# MesschieberV7.net
KiCad netlist of a schematic drawn in EAGLE
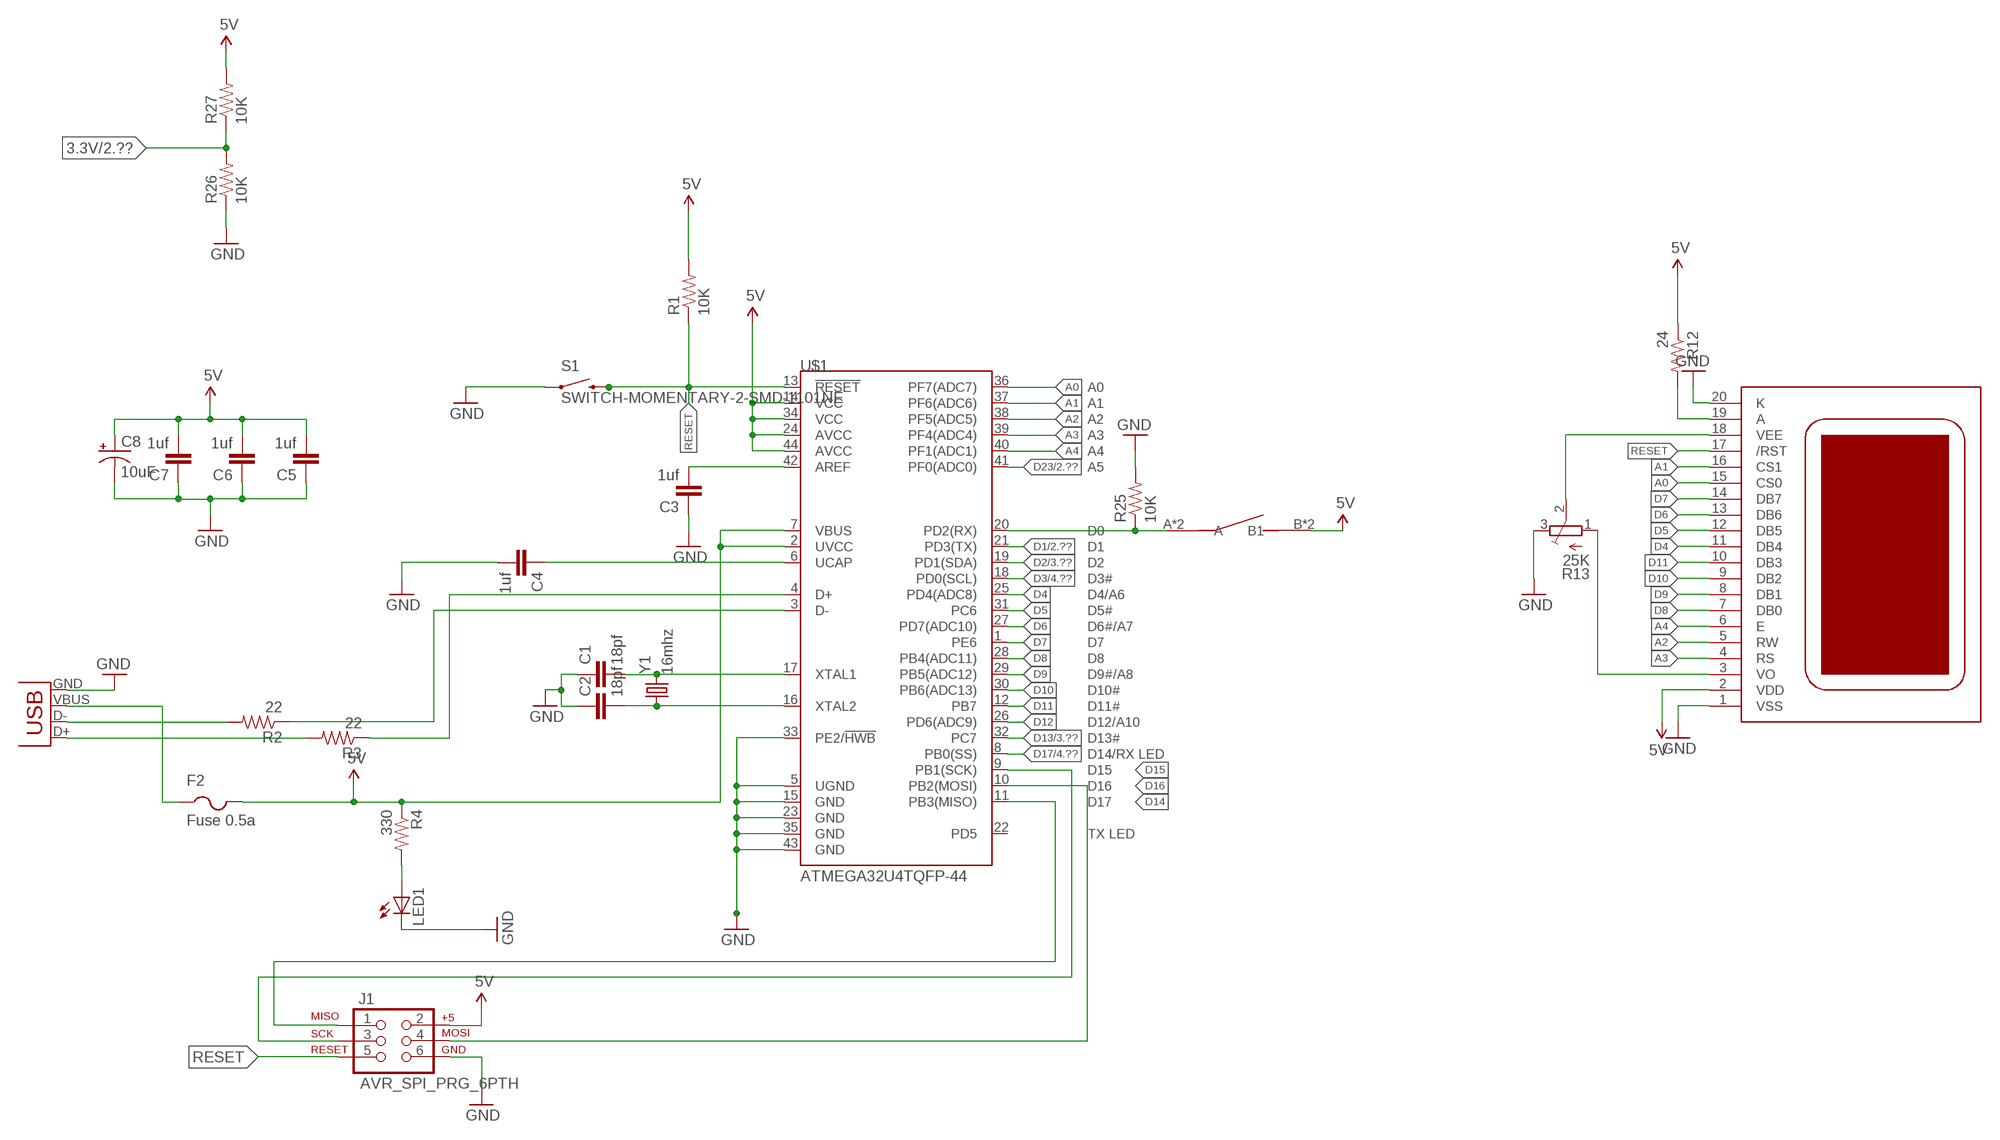
[diagram p0: schematic, sheet 1]
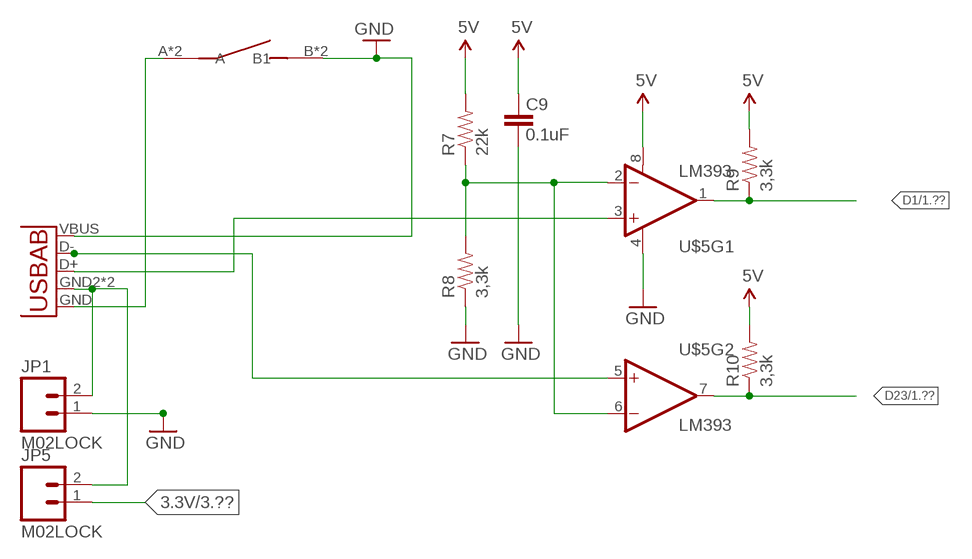
[diagram p1: schematic, sheet 2]
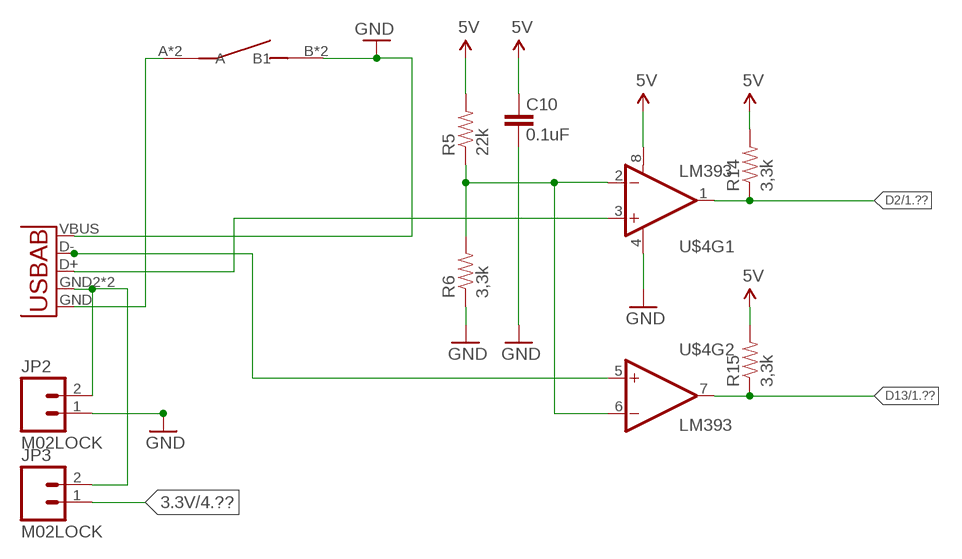
[diagram p2: schematic, sheet 3]
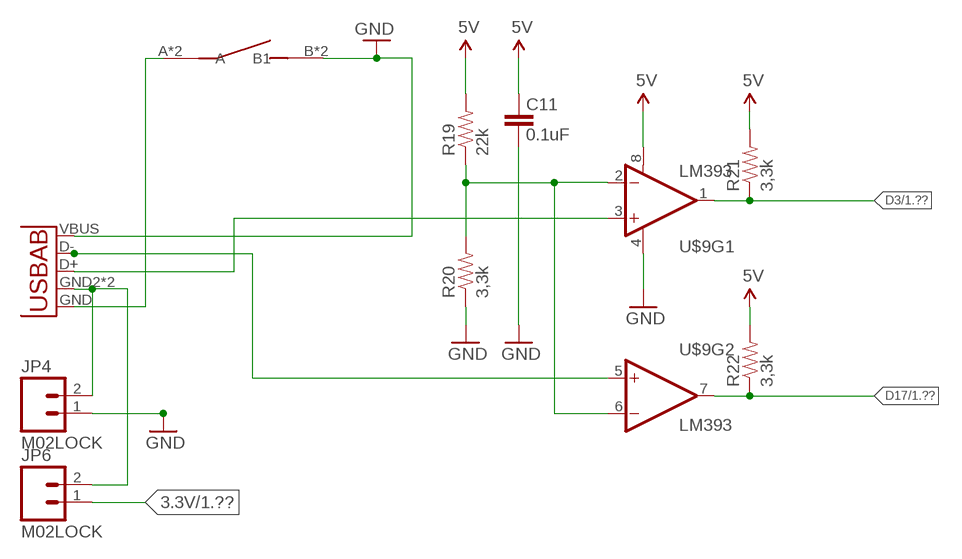
[diagram p3: schematic, sheet 4]

(export (version "E")
  (design (tool "Eeschema 10.0.6"))
  (components
    (comp (ref "C10")
      (value "0.1uF")
      (footprint "eagle-import:0805")
      (libsource (lib "eagle-import") (part "CAP0805"))
    )
    (comp (ref "JP2")
      (value "M02LOCK")
      (footprint "eagle-import:1X02_LOCK")
      (libsource (lib "eagle-import") (part "M02LOCK"))
    )
    (comp (ref "JP3")
      (value "M02LOCK")
      (footprint "eagle-import:1X02_LOCK")
      (libsource (lib "eagle-import") (part "M02LOCK"))
    )
    (comp (ref "R5")
      (value "22k")
      (footprint "eagle-import:0603")
      (libsource (lib "eagle-import") (part "RESISTOR0603"))
    )
    (comp (ref "R6")
      (value "3,3k")
      (footprint "eagle-import:0603")
      (libsource (lib "eagle-import") (part "RESISTOR0603"))
    )
    (comp (ref "R14")
      (value "3,3k")
      (footprint "eagle-import:0603")
      (libsource (lib "eagle-import") (part "RESISTOR0603"))
    )
    (comp (ref "R15")
      (value "3,3k")
      (footprint "eagle-import:0603")
      (libsource (lib "eagle-import") (part "RESISTOR0603"))
    )
    (comp (ref "U$4")
      (value "LM393")
      (footprint "eagle-import:SO08")
      (libsource (lib "eagle-import") (part "LM393"))
    )
    (comp (ref "U$6")
      (value "USB-A")
      (footprint "eagle-import:USB-A")
      (libsource (lib "eagle-import") (part "USB-A"))
    )
    (comp (ref "U$8")
      (value "TASTE_R3FTL6")
      (footprint "eagle-import:TASTE_R3FTL6")
      (libsource (lib "eagle-import") (part "TASTE_R3FTL6"))
    )
    (comp (ref "C1")
      (value "18pf")
      (footprint "eagle-import:0805")
      (libsource (lib "eagle-import") (part "SparkFun-Capacitors_CAP0805"))
    )
    (comp (ref "C2")
      (value "18pf")
      (footprint "eagle-import:0805")
      (libsource (lib "eagle-import") (part "SparkFun-Capacitors_CAP0805"))
    )
    (comp (ref "C3")
      (value "1uf")
      (footprint "eagle-import:0805")
      (libsource (lib "eagle-import") (part "SparkFun-Capacitors_CAP0805"))
    )
    (comp (ref "C4")
      (value "1uf")
      (footprint "eagle-import:0805")
      (libsource (lib "eagle-import") (part "SparkFun-Capacitors_CAP0805"))
    )
    (comp (ref "C5")
      (value "1uf")
      (footprint "eagle-import:0805")
      (libsource (lib "eagle-import") (part "SparkFun-Capacitors_CAP0805"))
    )
    (comp (ref "C6")
      (value "1uf")
      (footprint "eagle-import:0805")
      (libsource (lib "eagle-import") (part "SparkFun-Capacitors_CAP0805"))
    )
    (comp (ref "C7")
      (value "1uf")
      (footprint "eagle-import:0805")
      (libsource (lib "eagle-import") (part "SparkFun-Capacitors_CAP0805"))
    )
    (comp (ref "C8")
      (value "10uF")
      (footprint "eagle-import:EIA3528")
      (libsource (lib "eagle-import") (part "10UF-20V-10%(TANT)"))
    )
    (comp (ref "F2")
      (value "Fuse 0.5a")
      (footprint "eagle-import:1812")
      (libsource (lib "eagle-import") (part "PTCFUSE-1812"))
    )
    (comp (ref "J1")
      (value "AVR_SPI_PRG_6PTH")
      (footprint "eagle-import:2X3")
      (libsource (lib "eagle-import") (part "AVR_SPI_PRG_6PTH"))
    )
    (comp (ref "JP7")
      (value "USB-SMD-NS")
      (footprint "eagle-import:USB-MINIB-NOSTOP")
      (libsource (lib "eagle-import") (part "USB-SMD-NS"))
    )
    (comp (ref "LED1")
      (value "LEDSML0805")
      (footprint "eagle-import:SML0805")
      (libsource (lib "eagle-import") (part "LEDSML0805"))
    )
    (comp (ref "R1")
      (value "10K")
      (footprint "eagle-import:0603-RES")
      (libsource (lib "eagle-import") (part "RESISTOR0603-RES"))
    )
    (comp (ref "R2")
      (value "22")
      (footprint "eagle-import:0603")
      (libsource (lib "eagle-import") (part "RESISTOR0603"))
    )
    (comp (ref "R3")
      (value "22")
      (footprint "eagle-import:0603")
      (libsource (lib "eagle-import") (part "RESISTOR0603"))
    )
    (comp (ref "R4")
      (value "330")
      (footprint "eagle-import:0603")
      (libsource (lib "eagle-import") (part "RESISTOR0603"))
    )
    (comp (ref "R12")
      (value "24")
      (footprint "eagle-import:0603")
      (libsource (lib "eagle-import") (part "RESISTOR0603"))
    )
    (comp (ref "R13")
      (value "25K")
      (footprint "eagle-import:SM-42_43A")
      (libsource (lib "eagle-import") (part "TRIM_EU-SM-42/43A"))
    )
    (comp (ref "R25")
      (value "10K")
      (footprint "eagle-import:0603")
      (libsource (lib "eagle-import") (part "RESISTOR0603"))
    )
    (comp (ref "R26")
      (value "10K")
      (footprint "eagle-import:0805")
      (libsource (lib "eagle-import") (part "RESISTOR"))
    )
    (comp (ref "R27")
      (value "10K")
      (footprint "eagle-import:0805")
      (libsource (lib "eagle-import") (part "RESISTOR"))
    )
    (comp (ref "S1")
      (value "SWITCH-MOMENTARY-2-SMD-1101NE")
      (footprint "eagle-import:TACTILE-SWITCH-1101NE")
      (libsource (lib "eagle-import") (part "SWITCH-MOMENTARY-2-SMD-1101NE"))
    )
    (comp (ref "U$1")
      (value "ATMEGA32U4TQFP-44")
      (footprint "eagle-import:TQFP44")
      (libsource (lib "eagle-import") (part "ATMEGA32U4TQFP-44"))
    )
    (comp (ref "U$2")
      (value "TS12864A")
      (footprint "eagle-import:TS12864")
      (libsource (lib "eagle-import") (part "TS12864A"))
    )
    (comp (ref "U$12")
      (value "TASTE_R3FTL6")
      (footprint "eagle-import:TASTE_R3FTL6")
      (libsource (lib "eagle-import") (part "TASTE_R3FTL6"))
    )
    (comp (ref "Y1")
      (value "16mhz")
      (footprint "eagle-import:CRYSTAL-SMD-5X3")
      (libsource (lib "eagle-import") (part "CRYSTAL5X3"))
    )
    (comp (ref "C11")
      (value "0.1uF")
      (footprint "eagle-import:0805")
      (libsource (lib "eagle-import") (part "CAP0805"))
    )
    (comp (ref "JP4")
      (value "M02LOCK")
      (footprint "eagle-import:1X02_LOCK")
      (libsource (lib "eagle-import") (part "M02LOCK"))
    )
    (comp (ref "JP6")
      (value "M02LOCK")
      (footprint "eagle-import:1X02_LOCK")
      (libsource (lib "eagle-import") (part "M02LOCK"))
    )
    (comp (ref "R19")
      (value "22k")
      (footprint "eagle-import:0603")
      (libsource (lib "eagle-import") (part "RESISTOR0603"))
    )
    (comp (ref "R20")
      (value "3,3k")
      (footprint "eagle-import:0603")
      (libsource (lib "eagle-import") (part "RESISTOR0603"))
    )
    (comp (ref "R21")
      (value "3,3k")
      (footprint "eagle-import:0603")
      (libsource (lib "eagle-import") (part "RESISTOR0603"))
    )
    (comp (ref "R22")
      (value "3,3k")
      (footprint "eagle-import:0603")
      (libsource (lib "eagle-import") (part "RESISTOR0603"))
    )
    (comp (ref "U$9")
      (value "LM393")
      (footprint "eagle-import:SO08")
      (libsource (lib "eagle-import") (part "LM393"))
    )
    (comp (ref "U$10")
      (value "USB-A")
      (footprint "eagle-import:USB-A")
      (libsource (lib "eagle-import") (part "USB-A"))
    )
    (comp (ref "U$11")
      (value "TASTE_R3FTL6")
      (footprint "eagle-import:TASTE_R3FTL6")
      (libsource (lib "eagle-import") (part "TASTE_R3FTL6"))
    )
    (comp (ref "C9")
      (value "0.1uF")
      (footprint "eagle-import:0805")
      (libsource (lib "eagle-import") (part "CAP0805"))
    )
    (comp (ref "JP1")
      (value "M02LOCK")
      (footprint "eagle-import:1X02_LOCK")
      (libsource (lib "eagle-import") (part "M02LOCK"))
    )
    (comp (ref "JP5")
      (value "M02LOCK")
      (footprint "eagle-import:1X02_LOCK")
      (libsource (lib "eagle-import") (part "M02LOCK"))
    )
    (comp (ref "R7")
      (value "22k")
      (footprint "eagle-import:0603")
      (libsource (lib "eagle-import") (part "RESISTOR0603"))
    )
    (comp (ref "R8")
      (value "3,3k")
      (footprint "eagle-import:0603")
      (libsource (lib "eagle-import") (part "RESISTOR0603"))
    )
    (comp (ref "R9")
      (value "3,3k")
      (footprint "eagle-import:0603")
      (libsource (lib "eagle-import") (part "RESISTOR0603"))
    )
    (comp (ref "R10")
      (value "3,3k")
      (footprint "eagle-import:0603")
      (libsource (lib "eagle-import") (part "RESISTOR0603"))
    )
    (comp (ref "U$3")
      (value "TASTE_R3FTL6")
      (footprint "eagle-import:TASTE_R3FTL6")
      (libsource (lib "eagle-import") (part "TASTE_R3FTL6"))
    )
    (comp (ref "U$5")
      (value "LM393")
      (footprint "eagle-import:SO08")
      (libsource (lib "eagle-import") (part "LM393"))
    )
    (comp (ref "U$7")
      (value "USB-A")
      (footprint "eagle-import:USB-A")
      (libsource (lib "eagle-import") (part "USB-A"))
    )
  )
  (nets
    (net (code "1") (name "3.3V") (class "Default")
      (node (ref "JP3") (pin "1") (pinfunction "1_1") (pintype "passive"))
      (node (ref "JP5") (pin "1") (pinfunction "1_1") (pintype "passive"))
      (node (ref "JP6") (pin "1") (pinfunction "1_1") (pintype "passive"))
      (node (ref "R26") (pin "2") (pinfunction "2_2") (pintype "passive"))
      (node (ref "R27") (pin "1") (pinfunction "1_1") (pintype "passive"))
    )
    (net (code "2") (name "5V") (class "Default")
      (node (ref "C10") (pin "2") (pinfunction "2_2") (pintype "passive"))
      (node (ref "C11") (pin "2") (pinfunction "2_2") (pintype "passive"))
      (node (ref "C5") (pin "2") (pinfunction "2_2") (pintype "passive"))
      (node (ref "C6") (pin "2") (pinfunction "2_2") (pintype "passive"))
      (node (ref "C7") (pin "2") (pinfunction "2_2") (pintype "passive"))
      (node (ref "C8") (pin "A") (pinfunction "+_A") (pintype "passive"))
      (node (ref "C9") (pin "2") (pinfunction "2_2") (pintype "passive"))
      (node (ref "F2") (pin "2") (pinfunction "2_2") (pintype "passive"))
      (node (ref "J1") (pin "2") (pinfunction "2_2") (pintype "passive"))
      (node (ref "R1") (pin "2") (pinfunction "2_2") (pintype "passive"))
      (node (ref "R10") (pin "2") (pinfunction "2_2") (pintype "passive"))
      (node (ref "R12") (pin "1") (pinfunction "1_1") (pintype "passive"))
      (node (ref "R14") (pin "2") (pinfunction "2_2") (pintype "passive"))
      (node (ref "R15") (pin "2") (pinfunction "2_2") (pintype "passive"))
      (node (ref "R19") (pin "2") (pinfunction "2_2") (pintype "passive"))
      (node (ref "R21") (pin "2") (pinfunction "2_2") (pintype "passive"))
      (node (ref "R22") (pin "2") (pinfunction "2_2") (pintype "passive"))
      (node (ref "R27") (pin "2") (pinfunction "2_2") (pintype "passive"))
      (node (ref "R4") (pin "1") (pinfunction "1_1") (pintype "passive"))
      (node (ref "R5") (pin "2") (pinfunction "2_2") (pintype "passive"))
      (node (ref "R7") (pin "2") (pinfunction "2_2") (pintype "passive"))
      (node (ref "R9") (pin "2") (pinfunction "2_2") (pintype "passive"))
      (node (ref "U$1") (pin "14") (pinfunction "VCC_14") (pintype "bidirectional"))
      (node (ref "U$1") (pin "2") (pinfunction "UVCC_2") (pintype "bidirectional"))
      (node (ref "U$1") (pin "24") (pinfunction "AVCC_24") (pintype "bidirectional"))
      (node (ref "U$1") (pin "34") (pinfunction "VCC_34") (pintype "bidirectional"))
      (node (ref "U$1") (pin "44") (pinfunction "AVCC_44") (pintype "bidirectional"))
      (node (ref "U$1") (pin "7") (pinfunction "VBUS_7") (pintype "bidirectional"))
      (node (ref "U$12") (pin "B") (pinfunction "B1_B") (pintype "bidirectional"))
      (node (ref "U$12") (pin "B1") (pinfunction "B1_B1") (pintype "bidirectional"))
      (node (ref "U$2") (pin "2") (pinfunction "VDD_2") (pintype "power_in"))
      (node (ref "U$4") (pin "8") (pinfunction "V+_8") (pintype "power_in"))
      (node (ref "U$5") (pin "8") (pinfunction "V+_8") (pintype "power_in"))
      (node (ref "U$9") (pin "8") (pinfunction "V+_8") (pintype "power_in"))
    )
    (net (code "3") (name "A0") (class "Default")
      (node (ref "U$1") (pin "36") (pinfunction "PF7(ADC7)_36") (pintype "bidirectional"))
      (node (ref "U$2") (pin "15") (pinfunction "CS0_15") (pintype "input"))
    )
    (net (code "4") (name "A1") (class "Default")
      (node (ref "U$1") (pin "37") (pinfunction "PF6(ADC6)_37") (pintype "bidirectional"))
      (node (ref "U$2") (pin "16") (pinfunction "CS1_16") (pintype "input"))
    )
    (net (code "5") (name "A2") (class "Default")
      (node (ref "U$1") (pin "38") (pinfunction "PF5(ADC5)_38") (pintype "bidirectional"))
      (node (ref "U$2") (pin "5") (pinfunction "RW_5") (pintype "input"))
    )
    (net (code "6") (name "A3") (class "Default")
      (node (ref "U$1") (pin "39") (pinfunction "PF4(ADC4)_39") (pintype "bidirectional"))
      (node (ref "U$2") (pin "4") (pinfunction "RS_4") (pintype "input"))
    )
    (net (code "7") (name "A4") (class "Default")
      (node (ref "U$1") (pin "40") (pinfunction "PF1(ADC1)_40") (pintype "bidirectional"))
      (node (ref "U$2") (pin "6") (pinfunction "E_6") (pintype "input"))
    )
    (net (code "8") (name "D1") (class "Default")
      (node (ref "R9") (pin "1") (pinfunction "1_1") (pintype "passive"))
      (node (ref "U$1") (pin "21") (pinfunction "PD3(TX)_21") (pintype "bidirectional"))
      (node (ref "U$5") (pin "1") (pinfunction "OUT_1") (pintype "output"))
    )
    (net (code "9") (name "D2") (class "Default")
      (node (ref "R14") (pin "1") (pinfunction "1_1") (pintype "passive"))
      (node (ref "U$1") (pin "19") (pinfunction "PD1(SDA)_19") (pintype "bidirectional"))
      (node (ref "U$4") (pin "1") (pinfunction "OUT_1") (pintype "output"))
    )
    (net (code "10") (name "D3") (class "Default")
      (node (ref "R21") (pin "1") (pinfunction "1_1") (pintype "passive"))
      (node (ref "U$1") (pin "18") (pinfunction "PD0(SCL)_18") (pintype "bidirectional"))
      (node (ref "U$9") (pin "1") (pinfunction "OUT_1") (pintype "output"))
    )
    (net (code "11") (name "D4") (class "Default")
      (node (ref "U$1") (pin "25") (pinfunction "PD4(ADC8)_25") (pintype "bidirectional"))
      (node (ref "U$2") (pin "11") (pinfunction "DB4_11") (pintype "bidirectional"))
    )
    (net (code "12") (name "D5") (class "Default")
      (node (ref "U$1") (pin "31") (pinfunction "PC6_31") (pintype "bidirectional"))
      (node (ref "U$2") (pin "12") (pinfunction "DB5_12") (pintype "bidirectional"))
    )
    (net (code "13") (name "D6") (class "Default")
      (node (ref "U$1") (pin "27") (pinfunction "PD7(ADC10)_27") (pintype "bidirectional"))
      (node (ref "U$2") (pin "13") (pinfunction "DB6_13") (pintype "bidirectional"))
    )
    (net (code "14") (name "D7") (class "Default")
      (node (ref "U$1") (pin "1") (pinfunction "PE6_1") (pintype "bidirectional"))
      (node (ref "U$2") (pin "14") (pinfunction "DB7_14") (pintype "bidirectional"))
    )
    (net (code "15") (name "D8") (class "Default")
      (node (ref "U$1") (pin "28") (pinfunction "PB4(ADC11)_28") (pintype "bidirectional"))
      (node (ref "U$2") (pin "7") (pinfunction "DB0_7") (pintype "bidirectional"))
    )
    (net (code "16") (name "D9") (class "Default")
      (node (ref "U$1") (pin "29") (pinfunction "PB5(ADC12)_29") (pintype "bidirectional"))
      (node (ref "U$2") (pin "8") (pinfunction "DB1_8") (pintype "bidirectional"))
    )
    (net (code "17") (name "D10") (class "Default")
      (node (ref "U$1") (pin "30") (pinfunction "PB6(ADC13)_30") (pintype "bidirectional"))
      (node (ref "U$2") (pin "9") (pinfunction "DB2_9") (pintype "bidirectional"))
    )
    (net (code "18") (name "D11") (class "Default")
      (node (ref "U$1") (pin "12") (pinfunction "PB7_12") (pintype "bidirectional"))
      (node (ref "U$2") (pin "10") (pinfunction "DB3_10") (pintype "bidirectional"))
    )
    (net (code "19") (name "D12") (class "Default")
      (node (ref "U$1") (pin "26") (pinfunction "PD6(ADC9)_26") (pintype "bidirectional"))
    )
    (net (code "20") (name "D13") (class "Default")
      (node (ref "R15") (pin "1") (pinfunction "1_1") (pintype "passive"))
      (node (ref "U$1") (pin "32") (pinfunction "PC7_32") (pintype "bidirectional"))
      (node (ref "U$4") (pin "7") (pinfunction "OUT_7") (pintype "output"))
    )
    (net (code "21") (name "D14") (class "Default")
      (node (ref "J1") (pin "1") (pinfunction "1_1") (pintype "passive"))
      (node (ref "U$1") (pin "11") (pinfunction "PB3(MISO)_11") (pintype "bidirectional"))
    )
    (net (code "22") (name "D15") (class "Default")
      (node (ref "J1") (pin "3") (pinfunction "3_3") (pintype "passive"))
      (node (ref "U$1") (pin "9") (pinfunction "PB1(SCK)_9") (pintype "bidirectional"))
    )
    (net (code "23") (name "D16") (class "Default")
      (node (ref "J1") (pin "4") (pinfunction "4_4") (pintype "passive"))
      (node (ref "U$1") (pin "10") (pinfunction "PB2(MOSI)_10") (pintype "bidirectional"))
    )
    (net (code "24") (name "D17") (class "Default")
      (node (ref "R22") (pin "1") (pinfunction "1_1") (pintype "passive"))
      (node (ref "U$1") (pin "8") (pinfunction "PB0(SS)_8") (pintype "bidirectional"))
      (node (ref "U$9") (pin "7") (pinfunction "OUT_7") (pintype "output"))
    )
    (net (code "25") (name "D23") (class "Default")
      (node (ref "R10") (pin "1") (pinfunction "1_1") (pintype "passive"))
      (node (ref "U$1") (pin "41") (pinfunction "PF0(ADC0)_41") (pintype "bidirectional"))
      (node (ref "U$5") (pin "7") (pinfunction "OUT_7") (pintype "output"))
    )
    (net (code "26") (name "GND") (class "Default")
      (node (ref "C1") (pin "1") (pinfunction "1_1") (pintype "passive"))
      (node (ref "C10") (pin "1") (pinfunction "1_1") (pintype "passive"))
      (node (ref "C11") (pin "1") (pinfunction "1_1") (pintype "passive"))
      (node (ref "C2") (pin "1") (pinfunction "1_1") (pintype "passive"))
      (node (ref "C3") (pin "1") (pinfunction "1_1") (pintype "passive"))
      (node (ref "C4") (pin "2") (pinfunction "2_2") (pintype "passive"))
      (node (ref "C5") (pin "1") (pinfunction "1_1") (pintype "passive"))
      (node (ref "C6") (pin "1") (pinfunction "1_1") (pintype "passive"))
      (node (ref "C7") (pin "1") (pinfunction "1_1") (pintype "passive"))
      (node (ref "C8") (pin "C") (pinfunction "-_C") (pintype "passive"))
      (node (ref "C9") (pin "1") (pinfunction "1_1") (pintype "passive"))
      (node (ref "J1") (pin "6") (pinfunction "6_6") (pintype "passive"))
      (node (ref "JP1") (pin "1") (pinfunction "1_1") (pintype "passive"))
      (node (ref "JP2") (pin "1") (pinfunction "1_1") (pintype "passive"))
      (node (ref "JP4") (pin "1") (pinfunction "1_1") (pintype "passive"))
      (node (ref "JP7") (pin "GND") (pinfunction "GND_GND") (pintype "bidirectional"))
      (node (ref "LED1") (pin "C") (pinfunction "C_C") (pintype "passive"))
      (node (ref "R13") (pin "3") (pinfunction "E_3") (pintype "passive"))
      (node (ref "R20") (pin "1") (pinfunction "1_1") (pintype "passive"))
      (node (ref "R25") (pin "2") (pinfunction "2_2") (pintype "passive"))
      (node (ref "R26") (pin "1") (pinfunction "1_1") (pintype "passive"))
      (node (ref "R6") (pin "1") (pinfunction "1_1") (pintype "passive"))
      (node (ref "R8") (pin "1") (pinfunction "1_1") (pintype "passive"))
      (node (ref "S1") (pin "P$1") (pinfunction "1_P$1") (pintype "passive"))
      (node (ref "U$1") (pin "15") (pinfunction "GND_15") (pintype "bidirectional"))
      (node (ref "U$1") (pin "23") (pinfunction "GND_23") (pintype "bidirectional"))
      (node (ref "U$1") (pin "33") (pinfunction "PE2/~{HWB}_33") (pintype "bidirectional"))
      (node (ref "U$1") (pin "35") (pinfunction "GND_35") (pintype "bidirectional"))
      (node (ref "U$1") (pin "43") (pinfunction "GND_43") (pintype "bidirectional"))
      (node (ref "U$1") (pin "5") (pinfunction "UGND_5") (pintype "bidirectional"))
      (node (ref "U$10") (pin "VBUS") (pinfunction "VBUS_VBUS") (pintype "bidirectional"))
      (node (ref "U$11") (pin "B") (pinfunction "B1_B") (pintype "bidirectional"))
      (node (ref "U$11") (pin "B1") (pinfunction "B1_B1") (pintype "bidirectional"))
      (node (ref "U$2") (pin "1") (pinfunction "VSS_1") (pintype "power_in"))
      (node (ref "U$2") (pin "20") (pinfunction "K_20") (pintype "input"))
      (node (ref "U$3") (pin "B") (pinfunction "B1_B") (pintype "bidirectional"))
      (node (ref "U$3") (pin "B1") (pinfunction "B1_B1") (pintype "bidirectional"))
      (node (ref "U$4") (pin "4") (pinfunction "V-_4") (pintype "power_in"))
      (node (ref "U$5") (pin "4") (pinfunction "V-_4") (pintype "power_in"))
      (node (ref "U$6") (pin "VBUS") (pinfunction "VBUS_VBUS") (pintype "bidirectional"))
      (node (ref "U$7") (pin "VBUS") (pinfunction "VBUS_VBUS") (pintype "bidirectional"))
      (node (ref "U$8") (pin "B") (pinfunction "B1_B") (pintype "bidirectional"))
      (node (ref "U$8") (pin "B1") (pinfunction "B1_B1") (pintype "bidirectional"))
      (node (ref "U$9") (pin "4") (pinfunction "V-_4") (pintype "power_in"))
    )
    (net (code "27") (name "Net-(F2-Pad1)") (class "Default")
      (node (ref "F2") (pin "1") (pinfunction "1_1") (pintype "passive"))
      (node (ref "JP7") (pin "VBUS") (pinfunction "VBUS_VBUS") (pintype "bidirectional"))
    )
    (net (code "28") (name "Net-(JP1-Pad2)") (class "Default")
      (node (ref "JP1") (pin "2") (pinfunction "2_2") (pintype "passive"))
      (node (ref "JP5") (pin "2") (pinfunction "2_2") (pintype "passive"))
      (node (ref "U$7") (pin "GND2") (pinfunction "USBID_GND2") (pintype "bidirectional"))
      (node (ref "U$7") (pin "GND3") (pinfunction "USBID_GND3") (pintype "bidirectional"))
    )
    (net (code "29") (name "Net-(JP2-Pad2)") (class "Default")
      (node (ref "JP2") (pin "2") (pinfunction "2_2") (pintype "passive"))
      (node (ref "JP3") (pin "2") (pinfunction "2_2") (pintype "passive"))
      (node (ref "U$6") (pin "GND2") (pinfunction "USBID_GND2") (pintype "bidirectional"))
      (node (ref "U$6") (pin "GND3") (pinfunction "USBID_GND3") (pintype "bidirectional"))
    )
    (net (code "30") (name "Net-(JP4-Pad2)") (class "Default")
      (node (ref "JP4") (pin "2") (pinfunction "2_2") (pintype "passive"))
      (node (ref "JP6") (pin "2") (pinfunction "2_2") (pintype "passive"))
      (node (ref "U$10") (pin "GND2") (pinfunction "USBID_GND2") (pintype "bidirectional"))
      (node (ref "U$10") (pin "GND3") (pinfunction "USBID_GND3") (pintype "bidirectional"))
    )
    (net (code "31") (name "Net-(JP7-PadD+)") (class "Default")
      (node (ref "JP7") (pin "D+") (pinfunction "D+_D+") (pintype "bidirectional"))
      (node (ref "R3") (pin "2") (pinfunction "2_2") (pintype "passive"))
    )
    (net (code "32") (name "Net-(JP7-PadD-)") (class "Default")
      (node (ref "JP7") (pin "D-") (pinfunction "D-_D-") (pintype "bidirectional"))
      (node (ref "R2") (pin "2") (pinfunction "2_2") (pintype "passive"))
    )
    (net (code "33") (name "Net-(LED1-PadA)") (class "Default")
      (node (ref "LED1") (pin "A") (pinfunction "A_A") (pintype "passive"))
      (node (ref "R4") (pin "2") (pinfunction "2_2") (pintype "passive"))
    )
    (net (code "34") (name "Net-(R13-A)") (class "Default")
      (node (ref "R13") (pin "1") (pinfunction "A_1") (pintype "passive"))
      (node (ref "U$2") (pin "3") (pinfunction "VO_3") (pintype "input"))
    )
    (net (code "35") (name "Net-(R13-S)") (class "Default")
      (node (ref "R13") (pin "2") (pinfunction "S_2") (pintype "passive"))
      (node (ref "U$2") (pin "18") (pinfunction "VEE_18") (pintype "power_in"))
    )
    (net (code "36") (name "Net-(U$1-AREF)") (class "Default")
      (node (ref "C3") (pin "2") (pinfunction "2_2") (pintype "passive"))
      (node (ref "U$1") (pin "42") (pinfunction "AREF_42") (pintype "bidirectional"))
    )
    (net (code "37") (name "Net-(U$1-D+)") (class "Default")
      (node (ref "R3") (pin "1") (pinfunction "1_1") (pintype "passive"))
      (node (ref "U$1") (pin "4") (pinfunction "D+_4") (pintype "bidirectional"))
    )
    (net (code "38") (name "Net-(U$1-D-)") (class "Default")
      (node (ref "R2") (pin "1") (pinfunction "1_1") (pintype "passive"))
      (node (ref "U$1") (pin "3") (pinfunction "D-_3") (pintype "bidirectional"))
    )
    (net (code "39") (name "Net-(U$1-PD2(RX))") (class "Default")
      (node (ref "R25") (pin "1") (pinfunction "1_1") (pintype "passive"))
      (node (ref "U$1") (pin "20") (pinfunction "PD2(RX)_20") (pintype "bidirectional"))
      (node (ref "U$12") (pin "A") (pinfunction "A_A") (pintype "bidirectional"))
      (node (ref "U$12") (pin "A1") (pinfunction "A_A1") (pintype "bidirectional"))
    )
    (net (code "40") (name "Net-(U$1-UCAP)") (class "Default")
      (node (ref "C4") (pin "1") (pinfunction "1_1") (pintype "passive"))
      (node (ref "U$1") (pin "6") (pinfunction "UCAP_6") (pintype "bidirectional"))
    )
    (net (code "41") (name "Net-(U$1-XTAL1)") (class "Default")
      (node (ref "C1") (pin "2") (pinfunction "2_2") (pintype "passive"))
      (node (ref "U$1") (pin "17") (pinfunction "XTAL1_17") (pintype "bidirectional"))
      (node (ref "Y1") (pin "3") (pinfunction "2_3") (pintype "passive"))
    )
    (net (code "42") (name "Net-(U$1-XTAL2)") (class "Default")
      (node (ref "C2") (pin "2") (pinfunction "2_2") (pintype "passive"))
      (node (ref "U$1") (pin "16") (pinfunction "XTAL2_16") (pintype "bidirectional"))
      (node (ref "Y1") (pin "1") (pinfunction "1_1") (pintype "passive"))
    )
    (net (code "43") (name "Net-(U$2-A)") (class "Default")
      (node (ref "R12") (pin "2") (pinfunction "2_2") (pintype "passive"))
      (node (ref "U$2") (pin "19") (pinfunction "A_19") (pintype "power_in"))
    )
    (net (code "44") (name "Net-(U$3-A-PadA1)") (class "Default")
      (node (ref "U$3") (pin "A") (pinfunction "A_A") (pintype "bidirectional"))
      (node (ref "U$3") (pin "A1") (pinfunction "A_A1") (pintype "bidirectional"))
      (node (ref "U$7") (pin "GND") (pinfunction "GND_GND") (pintype "bidirectional"))
    )
    (net (code "45") (name "Net-(U$4A-+IN)") (class "Default")
      (node (ref "U$4") (pin "3") (pinfunction "+IN_3") (pintype "input"))
      (node (ref "U$6") (pin "D+") (pinfunction "D+_D+") (pintype "bidirectional"))
    )
    (net (code "46") (name "Net-(U$4A--IN)") (class "Default")
      (node (ref "R5") (pin "1") (pinfunction "1_1") (pintype "passive"))
      (node (ref "R6") (pin "2") (pinfunction "2_2") (pintype "passive"))
      (node (ref "U$4") (pin "2") (pinfunction "-IN_2") (pintype "input"))
      (node (ref "U$4") (pin "6") (pinfunction "-IN_6") (pintype "input"))
    )
    (net (code "47") (name "Net-(U$4B-+IN)") (class "Default")
      (node (ref "U$4") (pin "5") (pinfunction "+IN_5") (pintype "input"))
      (node (ref "U$6") (pin "D-") (pinfunction "D-_D-") (pintype "bidirectional"))
    )
    (net (code "48") (name "Net-(U$5A-+IN)") (class "Default")
      (node (ref "U$5") (pin "3") (pinfunction "+IN_3") (pintype "input"))
      (node (ref "U$7") (pin "D+") (pinfunction "D+_D+") (pintype "bidirectional"))
    )
    (net (code "49") (name "Net-(U$5A--IN)") (class "Default")
      (node (ref "R7") (pin "1") (pinfunction "1_1") (pintype "passive"))
      (node (ref "R8") (pin "2") (pinfunction "2_2") (pintype "passive"))
      (node (ref "U$5") (pin "2") (pinfunction "-IN_2") (pintype "input"))
      (node (ref "U$5") (pin "6") (pinfunction "-IN_6") (pintype "input"))
    )
    (net (code "50") (name "Net-(U$5B-+IN)") (class "Default")
      (node (ref "U$5") (pin "5") (pinfunction "+IN_5") (pintype "input"))
      (node (ref "U$7") (pin "D-") (pinfunction "D-_D-") (pintype "bidirectional"))
    )
    (net (code "51") (name "Net-(U$6-PadGND)") (class "Default")
      (node (ref "U$6") (pin "GND") (pinfunction "GND_GND") (pintype "bidirectional"))
      (node (ref "U$8") (pin "A") (pinfunction "A_A") (pintype "bidirectional"))
      (node (ref "U$8") (pin "A1") (pinfunction "A_A1") (pintype "bidirectional"))
    )
    (net (code "52") (name "Net-(U$9A-+IN)") (class "Default")
      (node (ref "U$10") (pin "D+") (pinfunction "D+_D+") (pintype "bidirectional"))
      (node (ref "U$9") (pin "3") (pinfunction "+IN_3") (pintype "input"))
    )
    (net (code "53") (name "Net-(U$9A--IN)") (class "Default")
      (node (ref "R19") (pin "1") (pinfunction "1_1") (pintype "passive"))
      (node (ref "R20") (pin "2") (pinfunction "2_2") (pintype "passive"))
      (node (ref "U$9") (pin "2") (pinfunction "-IN_2") (pintype "input"))
      (node (ref "U$9") (pin "6") (pinfunction "-IN_6") (pintype "input"))
    )
    (net (code "54") (name "Net-(U$9B-+IN)") (class "Default")
      (node (ref "U$10") (pin "D-") (pinfunction "D-_D-") (pintype "bidirectional"))
      (node (ref "U$9") (pin "5") (pinfunction "+IN_5") (pintype "input"))
    )
    (net (code "55") (name "Net-(U$10-PadGND)") (class "Default")
      (node (ref "U$10") (pin "GND") (pinfunction "GND_GND") (pintype "bidirectional"))
      (node (ref "U$11") (pin "A") (pinfunction "A_A") (pintype "bidirectional"))
      (node (ref "U$11") (pin "A1") (pinfunction "A_A1") (pintype "bidirectional"))
    )
    (net (code "56") (name "RESET") (class "Default")
      (node (ref "J1") (pin "5") (pinfunction "5_5") (pintype "passive"))
      (node (ref "R1") (pin "1") (pinfunction "1_1") (pintype "passive"))
      (node (ref "S1") (pin "P$2") (pinfunction "2_P$2") (pintype "passive"))
      (node (ref "U$1") (pin "13") (pinfunction "~{RESET}_13") (pintype "bidirectional"))
      (node (ref "U$2") (pin "17") (pinfunction "/RST_17") (pintype "input"))
    )
    (net (code "57") (name "unconnected-(U$1-PD5-Pad22)") (class "Default")
      (node (ref "U$1") (pin "22") (pinfunction "PD5_22") (pintype "bidirectional"))
    )
  )
)
